# Sheet1.net
KiCad netlist of a schematic drawn in Altium Designer
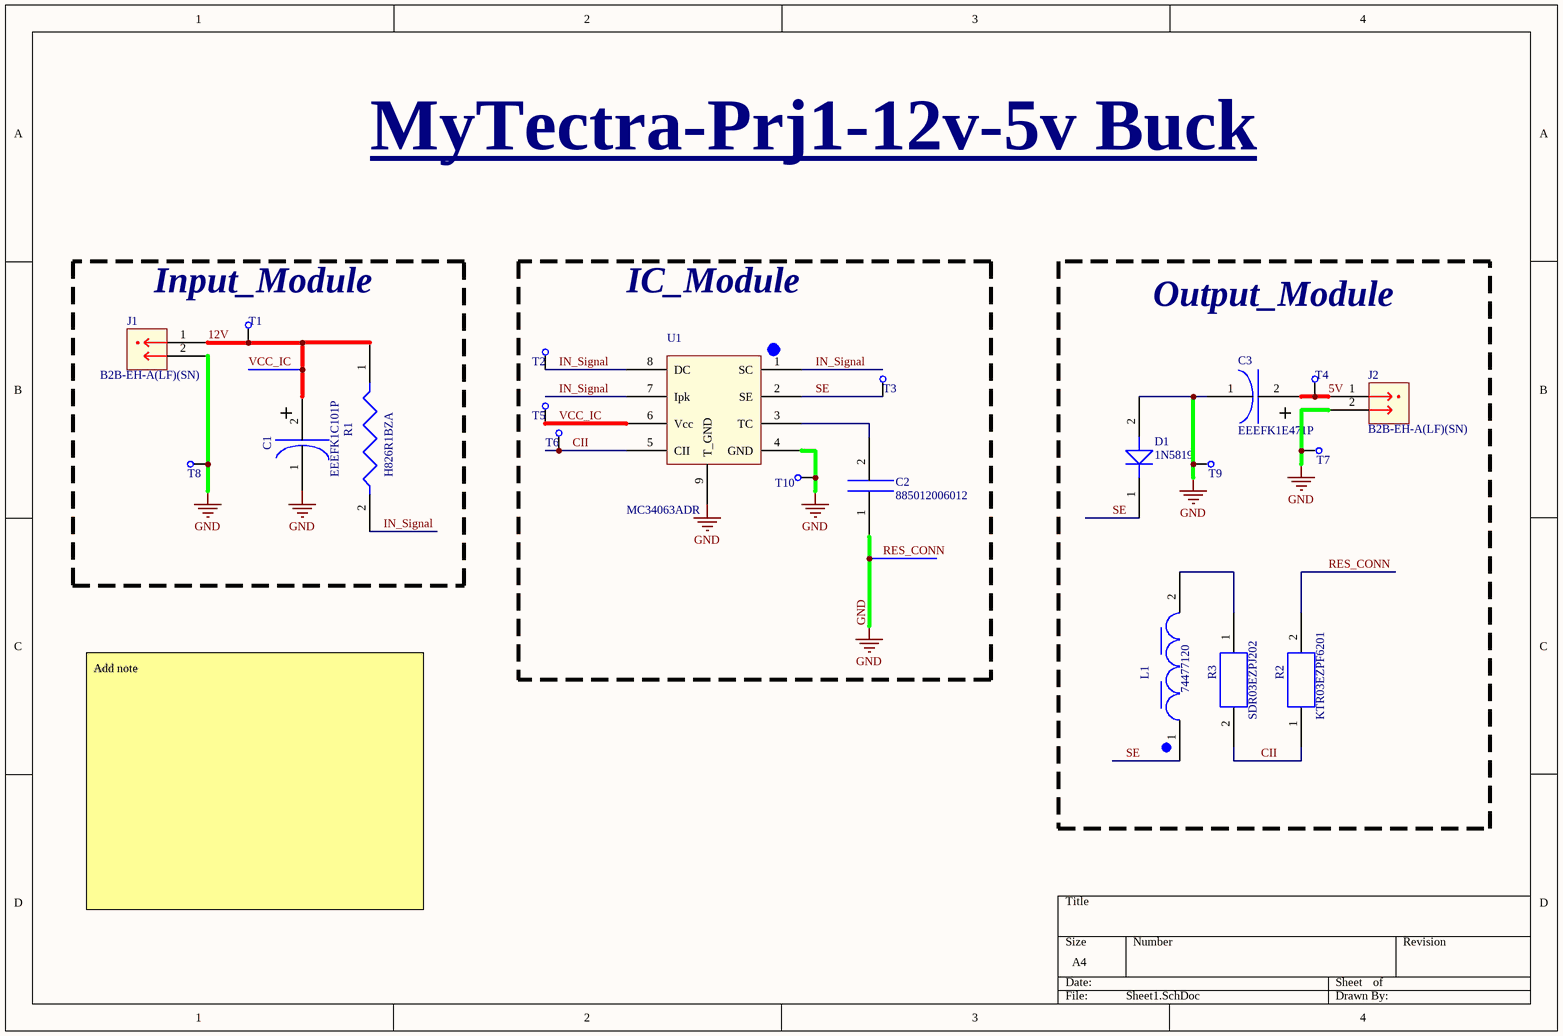
[diagram p0: Sheet1.SchDoc]

(export (version "E")
  (design (tool "Eeschema 10.0.6"))
  (components
    (comp (ref "C1")
      (value "EEEFK1C101P")
      (footprint "EEE-FK1C101P")
      (description "Cap Aluminum 100uF 16V 20% (6.3 X 5.8mm) SMD 240mA 2000 hr 105°C T/R")
      (fields (field (name "MANUFACTURER") "Panasonic"))
      (libsource (lib "Schlib1") (part "EEEFK1C101P"))
    )
    (comp (ref "C2")
      (value "885012006012")
      (footprint "885012006012")
      (description "Ceramic Capacitor 470pF, 10VDC, 0603, ±5 %")
      (fields (field (name "MANUFACTURER") "Wurth Electronics"))
      (libsource (lib "Schlib1") (part "885012006012"))
    )
    (comp (ref "C3")
      (value "EEEFK1E471P")
      (footprint "EEE-FK1E471P")
      (description "CAP ALUM 470UF 20% 25V SMD")
      (fields (field (name "MANUFACTURER") "Panasonic"))
      (libsource (lib "Schlib1") (part "EEEFK1E471P"))
    )
    (comp (ref "D1")
      (value "1N5819")
      (footprint "1N5819")
      (description "1N5819 Series Low Drop Power 1 A 40 V Schottky Rectifier Through Hole - DO-41")
      (fields (field (name "MANUFACTURER") "Taiwan Semiconductor"))
      (libsource (lib "Schlib1") (part "1N5819"))
    )
    (comp (ref "J1")
      (value "B2B-EH-A(LF)(SN)")
      (footprint "B2B-EH-A(LF)(SN)")
      (description "CONN HEADER EH TOP 2POS 2.5MM")
      (fields (field (name "MANUFACTURER") "JST"))
      (libsource (lib "Schlib1") (part "B2B-EH-A(LF)(SN)"))
    )
    (comp (ref "J2")
      (value "B2B-EH-A(LF)(SN)")
      (footprint "B2B-EH-A(LF)(SN)")
      (description "CONN HEADER EH TOP 2POS 2.5MM")
      (fields (field (name "MANUFACTURER") "JST"))
      (libsource (lib "") (part "B2B-EH-A(LF)(SN)_1"))
    )
    (comp (ref "L1")
      (value "74477120")
      (footprint "74477120_Inductor")
      (description "Power Choke Shielded Wirewound 100uH 20% 1KHz Ferrite 1.53A 160mOhm DCR T/R")
      (fields (field (name "MANUFACTURER") "Wurth Electronics"))
      (libsource (lib "Schlib1") (part "74477120"))
    )
    (comp (ref "R1")
      (value "H826R1BZA")
      (footprint "H826R1BZA")
      (description "Metal Film Resistors - Through Hole H8 26R1 0.1% 100PPM")
      (fields (field (name "MANUFACTURER") "TE Connectivity") (field (name "TOLERANCE") "0.1%"))
      (libsource (lib "Schlib1") (part "H826R1BZA"))
    )
    (comp (ref "R2")
      (value "KTR03EZPF6201")
      (footprint "KTR03EZPF6201")
      (description "Res High Voltage 0603 6.2K Ohm 1/10W 1% SMD")
      (fields (field (name "MANUFACTURER") "Rohm") (field (name "TOLERANCE") "1%"))
      (libsource (lib "Schlib1") (part "KTR03EZPF6201"))
    )
    (comp (ref "R3")
      (value "SDR03EZPJ202")
      (footprint "SDR03EZPJ202")
      (description "Res Thick Film 0603 2K Ohm 5% 0.3W ±200ppm/C Pad SMD Automotive T/R")
      (fields (field (name "MANUFACTURER") "Rohm"))
      (libsource (lib "Schlib1") (part "SDR03EZPJ202"))
    )
    (comp (ref "T1")
      (value "Test Pad")
      (footprint "Test Point")
      (libsource (lib "Schlib1") (part "Test_Pad"))
    )
    (comp (ref "T2")
      (value "Test Pad")
      (footprint "Test Point")
      (libsource (lib "Schlib1") (part "Test_Pad"))
    )
    (comp (ref "T3")
      (value "Test Pad")
      (footprint "Test Point")
      (libsource (lib "Schlib1") (part "Test_Pad"))
    )
    (comp (ref "T4")
      (value "Test Pad")
      (footprint "Test Point")
      (libsource (lib "Schlib1") (part "Test_Pad"))
    )
    (comp (ref "T5")
      (value "Test Pad")
      (footprint "Test Point")
      (libsource (lib "Schlib1") (part "Test_Pad"))
    )
    (comp (ref "T6")
      (value "Test Pad")
      (footprint "Test Point")
      (libsource (lib "Schlib1") (part "Test_Pad"))
    )
    (comp (ref "T7")
      (value "Test Pad")
      (footprint "Test Point")
      (libsource (lib "Schlib1") (part "Test_Pad"))
    )
    (comp (ref "T8")
      (value "Test Pad")
      (footprint "Test Point")
      (libsource (lib "Schlib1") (part "Test_Pad"))
    )
    (comp (ref "T9")
      (value "Test Pad")
      (footprint "Test Point")
      (libsource (lib "Schlib1") (part "Test_Pad"))
    )
    (comp (ref "T10")
      (value "Test Pad")
      (footprint "Test Point")
      (libsource (lib "Schlib1") (part "Test_Pad"))
    )
    (comp (ref "U1")
      (value "MC34063ADR")
      (footprint "MC34063ADR")
      (fields (field (name "MANUFACTURER") "Texas Instruments"))
      (libsource (lib "Schlib1") (part "MC34063ADR"))
    )
  )
  (nets
    (net (code "1") (name "/5V") (class "Default")
      (node (ref "C3") (pin "2") (pinfunction "2_2") (pintype "passive"))
      (node (ref "J2") (pin "1") (pinfunction "1_1") (pintype "passive"))
      (node (ref "T4") (pin "1") (pintype "passive"))
    )
    (net (code "2") (name "/12V") (class "Default")
      (node (ref "C1") (pin "2") (pinfunction "2_2") (pintype "passive"))
      (node (ref "J1") (pin "1") (pinfunction "1_1") (pintype "passive"))
      (node (ref "R1") (pin "1") (pinfunction "1_1") (pintype "passive"))
      (node (ref "T1") (pin "1") (pintype "passive"))
      (node (ref "T5") (pin "1") (pintype "passive"))
      (node (ref "U1") (pin "6") (pinfunction "Vcc_6") (pintype "passive"))
    )
    (net (code "3") (name "/CII") (class "Default")
      (node (ref "R2") (pin "1") (pinfunction "1_1") (pintype "passive"))
      (node (ref "R3") (pin "2") (pinfunction "2_2") (pintype "passive"))
      (node (ref "T6") (pin "1") (pintype "passive"))
      (node (ref "U1") (pin "5") (pinfunction "CII_5") (pintype "passive"))
    )
    (net (code "4") (name "/IN_Signal") (class "Default")
      (node (ref "R1") (pin "2") (pinfunction "2_2") (pintype "passive"))
      (node (ref "T2") (pin "1") (pintype "passive"))
      (node (ref "U1") (pin "1") (pinfunction "SC_1") (pintype "passive"))
      (node (ref "U1") (pin "7") (pinfunction "Ipk_7") (pintype "passive"))
      (node (ref "U1") (pin "8") (pinfunction "DC_8") (pintype "passive"))
    )
    (net (code "5") (name "/SE") (class "Default")
      (node (ref "D1") (pin "1") (pinfunction "1_1") (pintype "passive"))
      (node (ref "L1") (pin "1") (pinfunction "1_1") (pintype "passive"))
      (node (ref "T3") (pin "1") (pintype "passive"))
      (node (ref "U1") (pin "2") (pinfunction "SE_2") (pintype "passive"))
    )
    (net (code "6") (name "GND") (class "Default")
      (node (ref "C1") (pin "1") (pinfunction "1_1") (pintype "passive"))
      (node (ref "C2") (pin "1") (pinfunction "1_1") (pintype "passive"))
      (node (ref "C3") (pin "1") (pinfunction "1_1") (pintype "passive"))
      (node (ref "D1") (pin "2") (pinfunction "2_2") (pintype "passive"))
      (node (ref "J1") (pin "2") (pintype "passive"))
      (node (ref "J2") (pin "2") (pintype "passive"))
      (node (ref "R2") (pin "2") (pinfunction "2_2") (pintype "passive"))
      (node (ref "T10") (pin "1") (pintype "passive"))
      (node (ref "T7") (pin "1") (pintype "passive"))
      (node (ref "T8") (pin "1") (pintype "passive"))
      (node (ref "T9") (pin "1") (pintype "passive"))
      (node (ref "U1") (pin "4") (pinfunction "GND_4") (pintype "passive"))
      (node (ref "U1") (pin "9") (pinfunction "T_GND_9") (pintype "passive"))
    )
    (net (code "7") (name "Net-(L1-Pad2)") (class "Default")
      (node (ref "L1") (pin "2") (pinfunction "2_2") (pintype "passive"))
      (node (ref "R3") (pin "1") (pinfunction "1_1") (pintype "passive"))
    )
    (net (code "8") (name "Net-(U1-TC)") (class "Default")
      (node (ref "C2") (pin "2") (pinfunction "2_2") (pintype "passive"))
      (node (ref "U1") (pin "3") (pinfunction "TC_3") (pintype "passive"))
    )
  )
)
